# gprs.net
KiCad netlist of a schematic drawn in Altium Designer
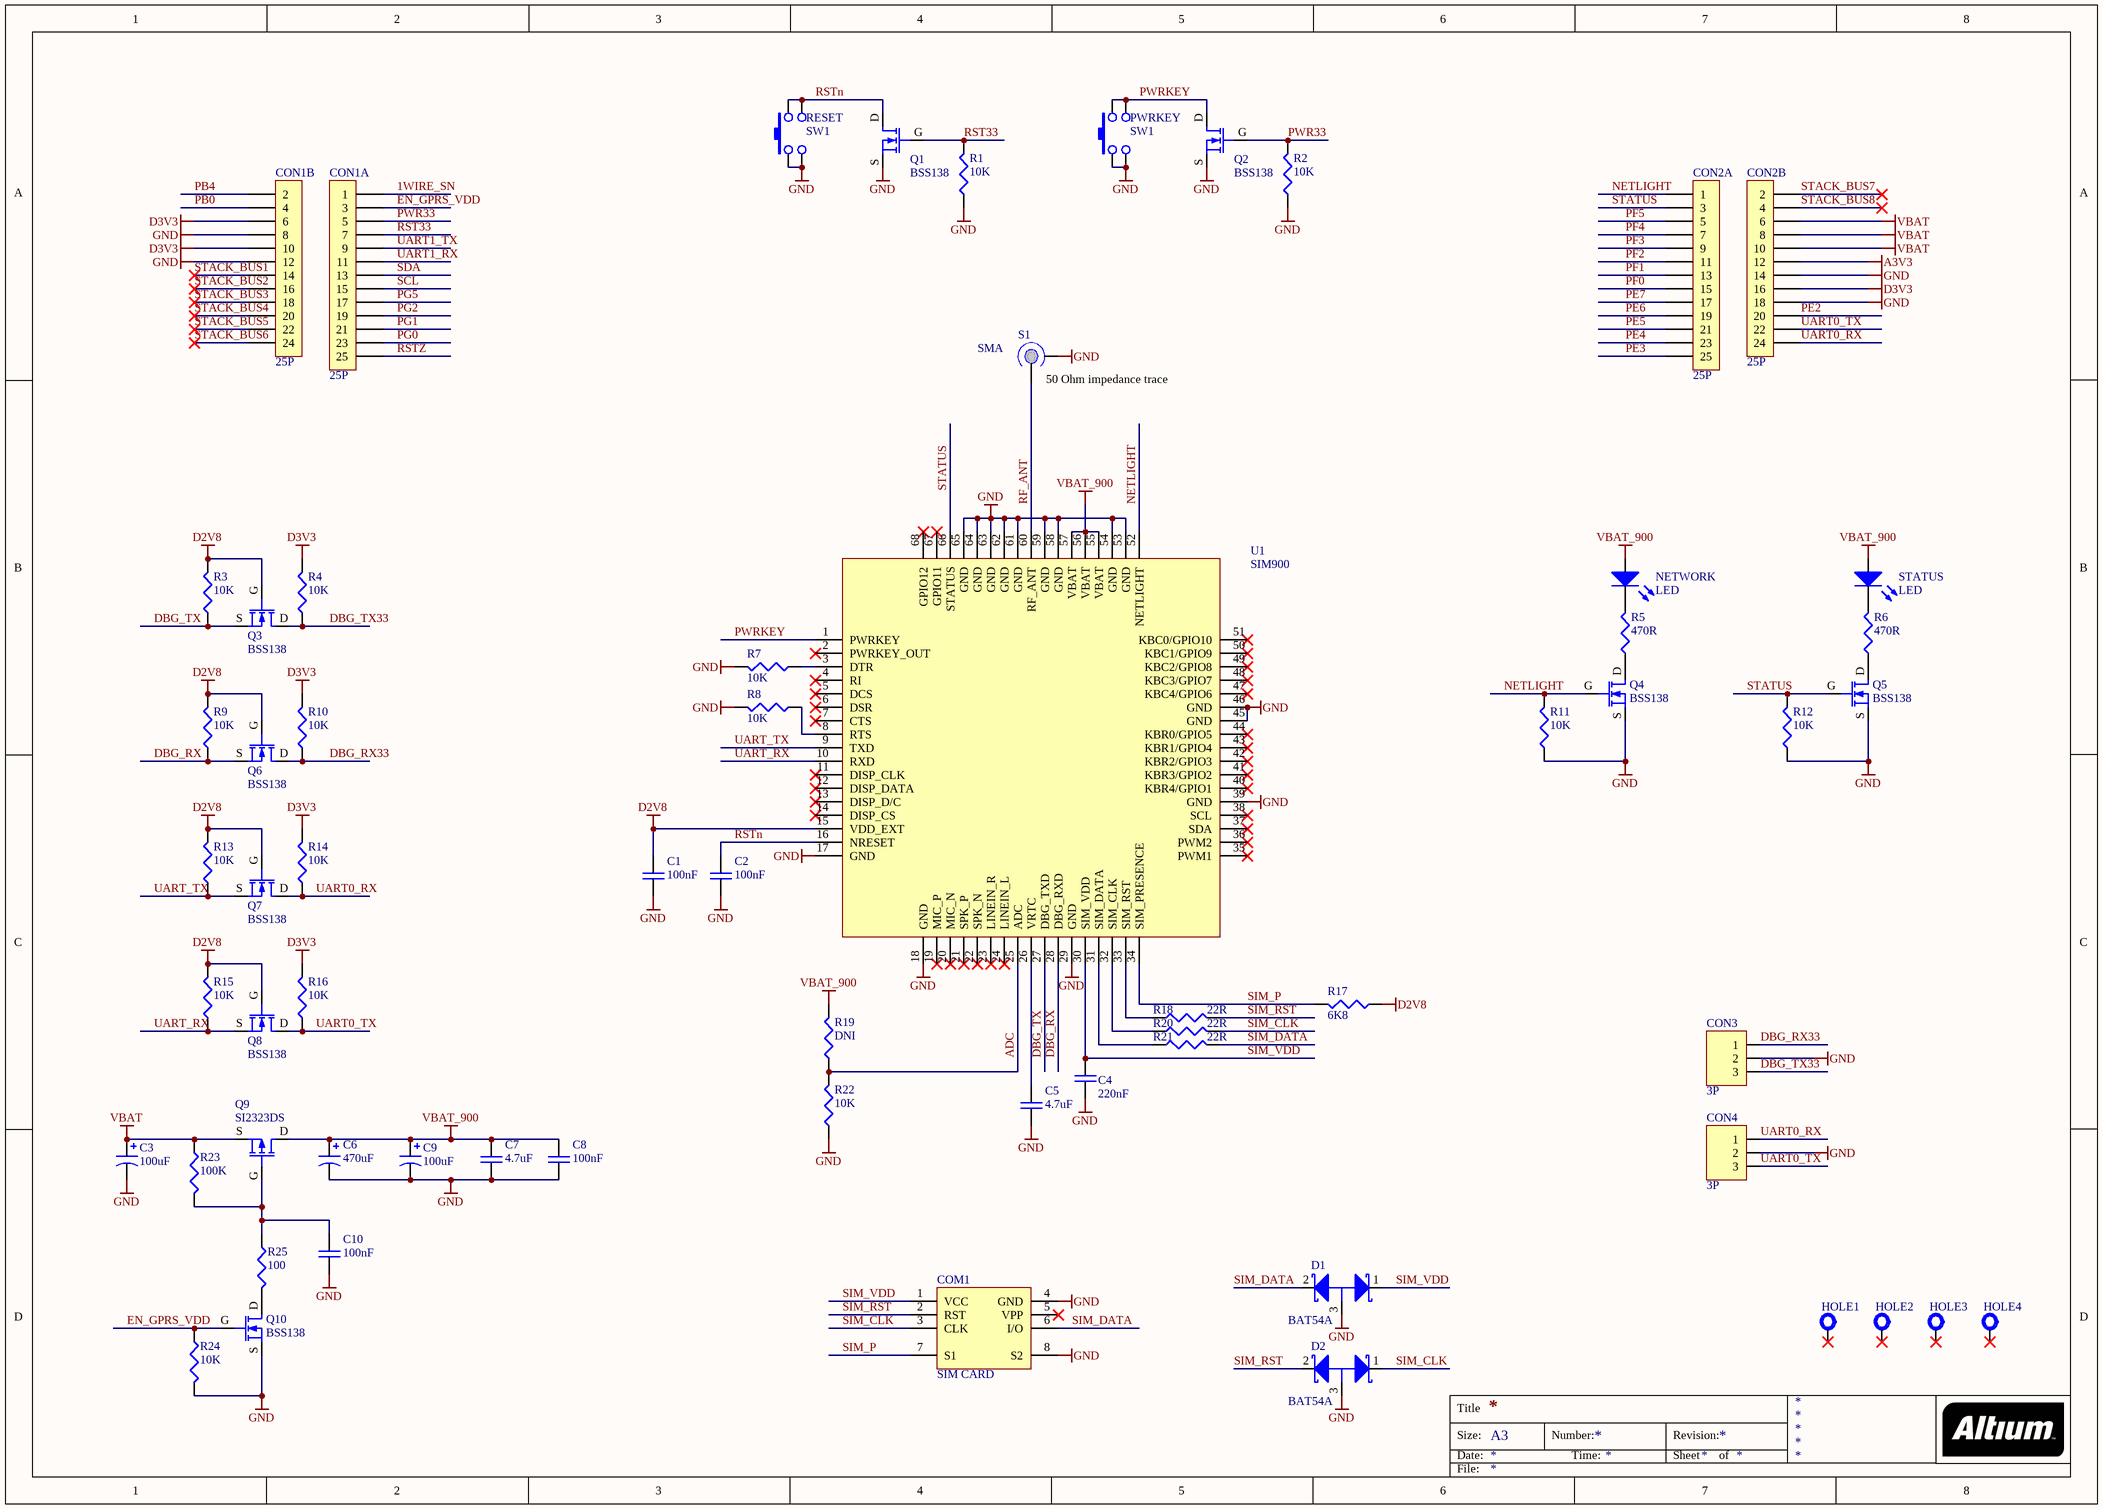
[diagram p0: gprs.SchDoc]

(export (version "E")
  (design (tool "Eeschema 10.0.6"))
  (components
    (comp (ref "C1")
      (value "100nF")
      (footprint "0603")
      (description "Capacitor")
      (fields (field (name "OWNER") "Nuno Brum"))
      (libsource (lib "Alcetronics_Devices") (part "CAP"))
    )
    (comp (ref "C2")
      (value "100nF")
      (footprint "0603")
      (description "Capacitor")
      (fields (field (name "OWNER") "Nuno Brum"))
      (libsource (lib "Alcetronics_Devices") (part "CAP"))
    )
    (comp (ref "C3")
      (value "100uF")
      (footprint "RADIAL-2.5MM")
      (description "Polarized Capacitor")
      (fields (field (name "OWNER") "Nuno Brum"))
      (libsource (lib "Alcetronics_Devices") (part "CAP POL"))
    )
    (comp (ref "C4")
      (value "220nF")
      (footprint "0603")
      (description "Capacitor")
      (fields (field (name "OWNER") "Nuno Brum"))
      (libsource (lib "Alcetronics_Devices") (part "CAP"))
    )
    (comp (ref "C5")
      (value "4.7uF")
      (footprint "0805")
      (description "Capacitor")
      (fields (field (name "OWNER") "Nuno Brum"))
      (libsource (lib "Alcetronics_Devices") (part "CAP"))
    )
    (comp (ref "C6")
      (value "470uF")
      (footprint "CASE-D")
      (description "Polarized Capacitor")
      (fields (field (name "OWNER") "Nuno Brum"))
      (libsource (lib "Alcetronics_Devices") (part "CAP POL"))
    )
    (comp (ref "C7")
      (value "4.7uF")
      (footprint "0805")
      (description "Capacitor")
      (fields (field (name "OWNER") "Nuno Brum"))
      (libsource (lib "Alcetronics_Devices") (part "CAP"))
    )
    (comp (ref "C8")
      (value "100nF")
      (footprint "0603")
      (description "Capacitor")
      (fields (field (name "OWNER") "Nuno Brum"))
      (libsource (lib "Alcetronics_Devices") (part "CAP"))
    )
    (comp (ref "C9")
      (value "100uF")
      (footprint "RADIAL-2.5MM")
      (description "Polarized Capacitor")
      (fields (field (name "OWNER") "Nuno Brum"))
      (libsource (lib "Alcetronics_Devices") (part "CAP POL"))
    )
    (comp (ref "C10")
      (value "100nF")
      (footprint "0603")
      (description "Capacitor")
      (fields (field (name "OWNER") "Nuno Brum"))
      (libsource (lib "Alcetronics_Devices") (part "CAP"))
    )
    (comp (ref "COM1")
      (value "SIM CARD")
      (footprint "Alcetronics_EM:SIMCARD-8")
      (description "SIMCARD holder")
      (fields (field (name "MANUFACTURER") "JAE Electronics"))
      (libsource (lib "Alcetronics_EM") (part "SIMCARD"))
    )
    (comp (ref "CON1")
      (value "25P")
      (footprint "DF9-25-MIRROR")
      (description "Connector 25 Pins")
      (fields (field (name "OWNER") "Ricardo Rodrigues"))
      (libsource (lib "Alcetronics_EM") (part "CON25"))
    )
    (comp (ref "CON2")
      (value "25P")
      (footprint "DF9-25-MIRROR")
      (description "Connector 25 Pins")
      (fields (field (name "OWNER") "Ricardo Rodrigues"))
      (libsource (lib "") (part "CON25_1"))
    )
    (comp (ref "CON3")
      (value "3P")
      (footprint "SIP-3")
      (description "Connector 3 pins")
      (fields (field (name "OWNER") "Rui Rebelo"))
      (libsource (lib "Alcetronics_EM") (part "CON03"))
    )
    (comp (ref "CON4")
      (value "3P")
      (footprint "SIP-3")
      (description "Connector 3 pins")
      (fields (field (name "OWNER") "Rui Rebelo"))
      (libsource (lib "Alcetronics_EM") (part "CON03"))
    )
    (comp (ref "D1")
      (value "BAT54A")
      (footprint "SOT-23")
      (description "Dual Schottky Barrier Diode")
      (fields (field (name "OWNER") "Luis Alves"))
      (libsource (lib "Alcetronics_Devices") (part "BAT54A"))
    )
    (comp (ref "D2")
      (value "BAT54A")
      (footprint "SOT-23")
      (description "Dual Schottky Barrier Diode")
      (fields (field (name "OWNER") "Luis Alves"))
      (libsource (lib "Alcetronics_Devices") (part "BAT54A"))
    )
    (comp (ref "HOLE1")
      (value "HOLE")
      (footprint "NPTH-3MM")
      (description "PCB Fixation Hole M3")
      (fields (field (name "OWNER") "Nuno Brum"))
      (libsource (lib "Alcetronics_EM") (part "PCB HOLE"))
    )
    (comp (ref "HOLE2")
      (value "HOLE")
      (footprint "NPTH-3MM")
      (description "PCB Fixation Hole M3")
      (fields (field (name "OWNER") "Nuno Brum"))
      (libsource (lib "Alcetronics_EM") (part "PCB HOLE"))
    )
    (comp (ref "HOLE3")
      (value "HOLE")
      (footprint "NPTH-3MM")
      (description "PCB Fixation Hole M3")
      (fields (field (name "OWNER") "Nuno Brum"))
      (libsource (lib "Alcetronics_EM") (part "PCB HOLE"))
    )
    (comp (ref "HOLE4")
      (value "HOLE")
      (footprint "NPTH-3MM")
      (description "PCB Fixation Hole M3")
      (fields (field (name "OWNER") "Nuno Brum"))
      (libsource (lib "Alcetronics_EM") (part "PCB HOLE"))
    )
    (comp (ref "NETWORK")
      (value "LED")
      (footprint "0805@DIODE")
      (description "Light emitting diode")
      (fields (field (name "OWNER") "Nuno Brum"))
      (libsource (lib "Alcetronics_Devices") (part "LED"))
    )
    (comp (ref "PWRKEY")
      (value "SW1")
      (footprint "MICROSWITCH")
      (description "Switch Push Button")
      (fields (field (name "OWNER") "Nuno Brum"))
      (libsource (lib "Alcetronics_EM") (part "SW1"))
    )
    (comp (ref "Q1")
      (value "BSS138")
      (footprint "SOT-23@GSD")
      (description "N-Channel Logic Level Enhancement Mode Field Effect Transistor")
      (fields (field (name "OWNER") "Nuno Brum"))
      (libsource (lib "Alcetronics_Devices") (part "MOSFET-N"))
    )
    (comp (ref "Q2")
      (value "BSS138")
      (footprint "SOT-23@GSD")
      (description "N-Channel Logic Level Enhancement Mode Field Effect Transistor")
      (fields (field (name "OWNER") "Nuno Brum"))
      (libsource (lib "Alcetronics_Devices") (part "MOSFET-N"))
    )
    (comp (ref "Q3")
      (value "BSS138")
      (footprint "SOT-23@GSD")
      (description "N-Channel Logic Level Enhancement Mode Field Effect Transistor")
      (fields (field (name "OWNER") "Nuno Brum"))
      (libsource (lib "Alcetronics_Devices") (part "MOSFET-N"))
    )
    (comp (ref "Q4")
      (value "BSS138")
      (footprint "SOT-23@GSD")
      (description "N-Channel Logic Level Enhancement Mode Field Effect Transistor")
      (fields (field (name "OWNER") "Nuno Brum"))
      (libsource (lib "Alcetronics_Devices") (part "MOSFET-N"))
    )
    (comp (ref "Q5")
      (value "BSS138")
      (footprint "SOT-23@GSD")
      (description "N-Channel Logic Level Enhancement Mode Field Effect Transistor")
      (fields (field (name "OWNER") "Nuno Brum"))
      (libsource (lib "Alcetronics_Devices") (part "MOSFET-N"))
    )
    (comp (ref "Q6")
      (value "BSS138")
      (footprint "SOT-23@GSD")
      (description "N-Channel Logic Level Enhancement Mode Field Effect Transistor")
      (fields (field (name "OWNER") "Nuno Brum"))
      (libsource (lib "Alcetronics_Devices") (part "MOSFET-N"))
    )
    (comp (ref "Q7")
      (value "BSS138")
      (footprint "SOT-23@GSD")
      (description "N-Channel Logic Level Enhancement Mode Field Effect Transistor")
      (fields (field (name "OWNER") "Nuno Brum"))
      (libsource (lib "Alcetronics_Devices") (part "MOSFET-N"))
    )
    (comp (ref "Q8")
      (value "BSS138")
      (footprint "SOT-23@GSD")
      (description "N-Channel Logic Level Enhancement Mode Field Effect Transistor")
      (fields (field (name "OWNER") "Nuno Brum"))
      (libsource (lib "Alcetronics_Devices") (part "MOSFET-N"))
    )
    (comp (ref "Q9")
      (value "SI2323DS")
      (footprint "SOT-23@GSD")
      (description "P-Channel Logic Level Enhancement Mode Field Effect Transistor")
      (fields (field (name "OWNER") "Nuno Brum"))
      (libsource (lib "Alcetronics_Devices") (part "MOSFET-P"))
    )
    (comp (ref "Q10")
      (value "BSS138")
      (footprint "SOT-23@GSD")
      (description "N-Channel Logic Level Enhancement Mode Field Effect Transistor")
      (fields (field (name "OWNER") "Nuno Brum"))
      (libsource (lib "Alcetronics_Devices") (part "MOSFET-N"))
    )
    (comp (ref "R1")
      (value "10K")
      (footprint "0603")
      (description "Resistor")
      (fields (field (name "OWNER") "Nuno Brum"))
      (libsource (lib "Alcetronics_Devices") (part "RES"))
    )
    (comp (ref "R2")
      (value "10K")
      (footprint "0603")
      (description "Resistor")
      (fields (field (name "OWNER") "Nuno Brum"))
      (libsource (lib "Alcetronics_Devices") (part "RES"))
    )
    (comp (ref "R3")
      (value "10K")
      (footprint "0603")
      (description "Resistor")
      (fields (field (name "OWNER") "Nuno Brum"))
      (libsource (lib "Alcetronics_Devices") (part "RES"))
    )
    (comp (ref "R4")
      (value "10K")
      (footprint "0603")
      (description "Resistor")
      (fields (field (name "OWNER") "Nuno Brum"))
      (libsource (lib "Alcetronics_Devices") (part "RES"))
    )
    (comp (ref "R5")
      (value "470R")
      (footprint "0603")
      (description "Resistor")
      (fields (field (name "OWNER") "Nuno Brum"))
      (libsource (lib "Alcetronics_Devices") (part "RES"))
    )
    (comp (ref "R6")
      (value "470R")
      (footprint "0603")
      (description "Resistor")
      (fields (field (name "OWNER") "Nuno Brum"))
      (libsource (lib "Alcetronics_Devices") (part "RES"))
    )
    (comp (ref "R7")
      (value "10K")
      (footprint "0603")
      (description "Resistor")
      (fields (field (name "OWNER") "Nuno Brum"))
      (libsource (lib "Alcetronics_Devices") (part "RES"))
    )
    (comp (ref "R8")
      (value "10K")
      (footprint "0603")
      (description "Resistor")
      (fields (field (name "OWNER") "Nuno Brum"))
      (libsource (lib "Alcetronics_Devices") (part "RES"))
    )
    (comp (ref "R9")
      (value "10K")
      (footprint "0603")
      (description "Resistor")
      (fields (field (name "OWNER") "Nuno Brum"))
      (libsource (lib "Alcetronics_Devices") (part "RES"))
    )
    (comp (ref "R10")
      (value "10K")
      (footprint "0603")
      (description "Resistor")
      (fields (field (name "OWNER") "Nuno Brum"))
      (libsource (lib "Alcetronics_Devices") (part "RES"))
    )
    (comp (ref "R11")
      (value "10K")
      (footprint "0603")
      (description "Resistor")
      (fields (field (name "OWNER") "Nuno Brum"))
      (libsource (lib "Alcetronics_Devices") (part "RES"))
    )
    (comp (ref "R12")
      (value "10K")
      (footprint "0603")
      (description "Resistor")
      (fields (field (name "OWNER") "Nuno Brum"))
      (libsource (lib "Alcetronics_Devices") (part "RES"))
    )
    (comp (ref "R13")
      (value "10K")
      (footprint "0603")
      (description "Resistor")
      (fields (field (name "OWNER") "Nuno Brum"))
      (libsource (lib "Alcetronics_Devices") (part "RES"))
    )
    (comp (ref "R14")
      (value "10K")
      (footprint "0603")
      (description "Resistor")
      (fields (field (name "OWNER") "Nuno Brum"))
      (libsource (lib "Alcetronics_Devices") (part "RES"))
    )
    (comp (ref "R15")
      (value "10K")
      (footprint "0603")
      (description "Resistor")
      (fields (field (name "OWNER") "Nuno Brum"))
      (libsource (lib "Alcetronics_Devices") (part "RES"))
    )
    (comp (ref "R16")
      (value "10K")
      (footprint "0603")
      (description "Resistor")
      (fields (field (name "OWNER") "Nuno Brum"))
      (libsource (lib "Alcetronics_Devices") (part "RES"))
    )
    (comp (ref "R17")
      (value "6K8")
      (footprint "0603")
      (description "Resistor")
      (fields (field (name "OWNER") "Nuno Brum"))
      (libsource (lib "Alcetronics_Devices") (part "RES"))
    )
    (comp (ref "R18")
      (value "22R")
      (footprint "0603")
      (description "Resistor")
      (fields (field (name "OWNER") "Nuno Brum"))
      (libsource (lib "Alcetronics_Devices") (part "RES"))
    )
    (comp (ref "R19")
      (value "DNI")
      (footprint "0603")
      (description "Resistor")
      (fields (field (name "OWNER") "Nuno Brum"))
      (libsource (lib "Alcetronics_Devices") (part "RES"))
    )
    (comp (ref "R20")
      (value "22R")
      (footprint "0603")
      (description "Resistor")
      (fields (field (name "OWNER") "Nuno Brum"))
      (libsource (lib "Alcetronics_Devices") (part "RES"))
    )
    (comp (ref "R21")
      (value "22R")
      (footprint "0603")
      (description "Resistor")
      (fields (field (name "OWNER") "Nuno Brum"))
      (libsource (lib "Alcetronics_Devices") (part "RES"))
    )
    (comp (ref "R22")
      (value "10K")
      (footprint "0603")
      (description "Resistor")
      (fields (field (name "OWNER") "Nuno Brum"))
      (libsource (lib "Alcetronics_Devices") (part "RES"))
    )
    (comp (ref "R23")
      (value "100K")
      (footprint "0603")
      (description "Resistor")
      (fields (field (name "OWNER") "Nuno Brum"))
      (libsource (lib "Alcetronics_Devices") (part "RES"))
    )
    (comp (ref "R24")
      (value "10K")
      (footprint "0603")
      (description "Resistor")
      (fields (field (name "OWNER") "Nuno Brum"))
      (libsource (lib "Alcetronics_Devices") (part "RES"))
    )
    (comp (ref "R25")
      (value "100")
      (footprint "0603")
      (description "Resistor")
      (fields (field (name "OWNER") "Nuno Brum"))
      (libsource (lib "Alcetronics_Devices") (part "RES"))
    )
    (comp (ref "RESET")
      (value "SW1")
      (footprint "MICROSWITCH")
      (description "Switch Push Button")
      (fields (field (name "OWNER") "Nuno Brum"))
      (libsource (lib "Alcetronics_EM") (part "SW1"))
    )
    (comp (ref "S1")
      (value "SMA")
      (footprint "SMA-JOHNSON-SCREW")
      (description "SMA to PCB - Coaxial connector")
      (fields (field (name "OWNER") "Nuno Brum"))
      (libsource (lib "Alcetronics_EM") (part "SMA"))
    )
    (comp (ref "STATUS")
      (value "LED")
      (footprint "0805@DIODE")
      (description "Light emitting diode")
      (fields (field (name "OWNER") "Nuno Brum"))
      (libsource (lib "Alcetronics_Devices") (part "LED"))
    )
    (comp (ref "U1") (value "SIM900") (footprint "SIM900") (libsource (lib "Alcetronics_IC") (part "SIM900")))
  )
  (nets
    (net (code "1") (name "/1WIRE_SN") (class "Default")
      (node (ref "CON1") (pin "1") (pinfunction "1_1") (pintype "passive"))
    )
    (net (code "2") (name "/ADC") (class "Default")
      (node (ref "R19") (pin "1") (pinfunction "1_1") (pintype "passive"))
      (node (ref "R22") (pin "2") (pinfunction "2_2") (pintype "passive"))
      (node (ref "U1") (pin "25") (pinfunction "ADC_25") (pintype "passive"))
    )
    (net (code "3") (name "/DBG_RX") (class "Default")
      (node (ref "Q6") (pin "S") (pinfunction "S_S") (pintype "passive"))
      (node (ref "R9") (pin "1") (pinfunction "1_1") (pintype "passive"))
      (node (ref "U1") (pin "28") (pinfunction "DBG_RXD_28") (pintype "passive"))
    )
    (net (code "4") (name "/DBG_RX33") (class "Default")
      (node (ref "CON3") (pin "1") (pinfunction "1_1") (pintype "passive"))
      (node (ref "Q6") (pin "D") (pinfunction "D_D") (pintype "passive"))
      (node (ref "R10") (pin "1") (pinfunction "1_1") (pintype "passive"))
    )
    (net (code "5") (name "/DBG_TX") (class "Default")
      (node (ref "Q3") (pin "S") (pinfunction "S_S") (pintype "passive"))
      (node (ref "R3") (pin "1") (pinfunction "1_1") (pintype "passive"))
      (node (ref "U1") (pin "27") (pinfunction "DBG_TXD_27") (pintype "passive"))
    )
    (net (code "6") (name "/DBG_TX33") (class "Default")
      (node (ref "CON3") (pin "3") (pinfunction "3_3") (pintype "passive"))
      (node (ref "Q3") (pin "D") (pinfunction "D_D") (pintype "passive"))
      (node (ref "R4") (pin "1") (pinfunction "1_1") (pintype "passive"))
    )
    (net (code "7") (name "/EN_GPRS_VDD") (class "Default")
      (node (ref "CON1") (pin "3") (pinfunction "3_3") (pintype "passive"))
      (node (ref "Q10") (pin "G") (pinfunction "G_G") (pintype "passive"))
      (node (ref "R24") (pin "1") (pinfunction "1_1") (pintype "passive"))
    )
    (net (code "8") (name "/NETLIGHT") (class "Default")
      (node (ref "CON2") (pin "1") (pinfunction "1_1") (pintype "passive"))
      (node (ref "Q4") (pin "G") (pinfunction "G_G") (pintype "passive"))
      (node (ref "R11") (pin "2") (pinfunction "2_2") (pintype "passive"))
      (node (ref "U1") (pin "52") (pinfunction "NETLIGHT_52") (pintype "passive"))
    )
    (net (code "9") (name "/PB0") (class "Default")
      (node (ref "CON1") (pin "4") (pinfunction "4_4") (pintype "passive"))
    )
    (net (code "10") (name "/PB4") (class "Default")
      (node (ref "CON1") (pin "2") (pinfunction "2_2") (pintype "passive"))
    )
    (net (code "11") (name "/PE2") (class "Default")
      (node (ref "CON2") (pin "20") (pinfunction "20_20") (pintype "passive"))
    )
    (net (code "12") (name "/PE3") (class "Default")
      (node (ref "CON2") (pin "25") (pinfunction "25_25") (pintype "passive"))
    )
    (net (code "13") (name "/PE4") (class "Default")
      (node (ref "CON2") (pin "23") (pinfunction "23_23") (pintype "passive"))
    )
    (net (code "14") (name "/PE5") (class "Default")
      (node (ref "CON2") (pin "21") (pinfunction "21_21") (pintype "passive"))
    )
    (net (code "15") (name "/PE6") (class "Default")
      (node (ref "CON2") (pin "19") (pinfunction "19_19") (pintype "passive"))
    )
    (net (code "16") (name "/PE7") (class "Default")
      (node (ref "CON2") (pin "17") (pinfunction "17_17") (pintype "passive"))
    )
    (net (code "17") (name "/PF0") (class "Default")
      (node (ref "CON2") (pin "15") (pinfunction "15_15") (pintype "passive"))
    )
    (net (code "18") (name "/PF1") (class "Default")
      (node (ref "CON2") (pin "13") (pinfunction "13_13") (pintype "passive"))
    )
    (net (code "19") (name "/PF2") (class "Default")
      (node (ref "CON2") (pin "11") (pinfunction "11_11") (pintype "passive"))
    )
    (net (code "20") (name "/PF3") (class "Default")
      (node (ref "CON2") (pin "9") (pinfunction "9_9") (pintype "passive"))
    )
    (net (code "21") (name "/PF4") (class "Default")
      (node (ref "CON2") (pin "7") (pinfunction "7_7") (pintype "passive"))
    )
    (net (code "22") (name "/PF5") (class "Default")
      (node (ref "CON2") (pin "5") (pinfunction "5_5") (pintype "passive"))
    )
    (net (code "23") (name "/PG0") (class "Default")
      (node (ref "CON1") (pin "23") (pinfunction "23_23") (pintype "passive"))
    )
    (net (code "24") (name "/PG1") (class "Default")
      (node (ref "CON1") (pin "21") (pinfunction "21_21") (pintype "passive"))
    )
    (net (code "25") (name "/PG2") (class "Default")
      (node (ref "CON1") (pin "19") (pinfunction "19_19") (pintype "passive"))
    )
    (net (code "26") (name "/PG5") (class "Default")
      (node (ref "CON1") (pin "17") (pinfunction "17_17") (pintype "passive"))
    )
    (net (code "27") (name "/PWR33") (class "Default")
      (node (ref "CON1") (pin "5") (pinfunction "5_5") (pintype "passive"))
      (node (ref "Q2") (pin "G") (pinfunction "G_G") (pintype "passive"))
      (node (ref "R2") (pin "2") (pinfunction "2_2") (pintype "passive"))
    )
    (net (code "28") (name "/PWRKEY") (class "Default")
      (node (ref "PWRKEY") (pin "2") (pinfunction "2_2") (pintype "passive"))
      (node (ref "PWRKEY") (pin "4") (pinfunction "4_4") (pintype "passive"))
      (node (ref "Q2") (pin "D") (pinfunction "D_D") (pintype "passive"))
      (node (ref "U1") (pin "1") (pinfunction "PWRKEY_1") (pintype "passive"))
    )
    (net (code "29") (name "/RF_ANT") (class "Default")
      (node (ref "S1") (pin "1") (pinfunction "SIG_1") (pintype "passive"))
      (node (ref "U1") (pin "60") (pinfunction "RF_ANT_60") (pintype "passive"))
    )
    (net (code "30") (name "/RST33") (class "Default")
      (node (ref "CON1") (pin "7") (pinfunction "7_7") (pintype "passive"))
      (node (ref "Q1") (pin "G") (pinfunction "G_G") (pintype "passive"))
      (node (ref "R1") (pin "2") (pinfunction "2_2") (pintype "passive"))
    )
    (net (code "31") (name "/RSTZ") (class "Default")
      (node (ref "CON1") (pin "25") (pinfunction "25_25") (pintype "passive"))
    )
    (net (code "32") (name "/RSTn") (class "Default")
      (node (ref "C2") (pin "2") (pinfunction "2_2") (pintype "passive"))
      (node (ref "Q1") (pin "D") (pinfunction "D_D") (pintype "passive"))
      (node (ref "RESET") (pin "2") (pinfunction "2_2") (pintype "passive"))
      (node (ref "RESET") (pin "4") (pinfunction "4_4") (pintype "passive"))
      (node (ref "U1") (pin "16") (pinfunction "NRESET_16") (pintype "passive"))
    )
    (net (code "33") (name "/SCL") (class "Default")
      (node (ref "CON1") (pin "15") (pinfunction "15_15") (pintype "passive"))
    )
    (net (code "34") (name "/SDA") (class "Default")
      (node (ref "CON1") (pin "13") (pinfunction "13_13") (pintype "passive"))
    )
    (net (code "35") (name "/SIM_CLK") (class "Default")
      (node (ref "COM1") (pin "3") (pinfunction "CLK_3") (pintype "passive"))
      (node (ref "D2") (pin "1") (pinfunction "A1_1") (pintype "passive"))
      (node (ref "R20") (pin "2") (pinfunction "2_2") (pintype "passive"))
    )
    (net (code "36") (name "/SIM_DATA") (class "Default")
      (node (ref "COM1") (pin "6") (pinfunction "I/O_6") (pintype "passive"))
      (node (ref "D1") (pin "2") (pinfunction "A2_2") (pintype "passive"))
      (node (ref "R21") (pin "2") (pinfunction "2_2") (pintype "passive"))
    )
    (net (code "37") (name "/SIM_P") (class "Default")
      (node (ref "COM1") (pin "7") (pinfunction "S1_7") (pintype "passive"))
      (node (ref "R17") (pin "2") (pinfunction "2_2") (pintype "passive"))
      (node (ref "U1") (pin "34") (pinfunction "SIM_PRESENCE_34") (pintype "passive"))
    )
    (net (code "38") (name "/SIM_RST") (class "Default")
      (node (ref "COM1") (pin "2") (pinfunction "RST_2") (pintype "passive"))
      (node (ref "D2") (pin "2") (pinfunction "A2_2") (pintype "passive"))
      (node (ref "R18") (pin "2") (pinfunction "2_2") (pintype "passive"))
    )
    (net (code "39") (name "/SIM_VDD") (class "Default")
      (node (ref "C4") (pin "2") (pinfunction "2_2") (pintype "passive"))
      (node (ref "COM1") (pin "1") (pinfunction "VCC_1") (pintype "passive"))
      (node (ref "D1") (pin "1") (pinfunction "A1_1") (pintype "passive"))
      (node (ref "U1") (pin "30") (pinfunction "SIM_VDD_30") (pintype "passive"))
    )
    (net (code "40") (name "/STACK_BUS1") (class "Default")
      (node (ref "CON1") (pin "14") (pinfunction "14_14") (pintype "passive+no_connect"))
    )
    (net (code "41") (name "/STACK_BUS2") (class "Default")
      (node (ref "CON1") (pin "16") (pinfunction "16_16") (pintype "passive+no_connect"))
    )
    (net (code "42") (name "/STACK_BUS3") (class "Default")
      (node (ref "CON1") (pin "18") (pinfunction "18_18") (pintype "passive+no_connect"))
    )
    (net (code "43") (name "/STACK_BUS4") (class "Default")
      (node (ref "CON1") (pin "20") (pinfunction "20_20") (pintype "passive+no_connect"))
    )
    (net (code "44") (name "/STACK_BUS5") (class "Default")
      (node (ref "CON1") (pin "22") (pinfunction "22_22") (pintype "passive+no_connect"))
    )
    (net (code "45") (name "/STACK_BUS6") (class "Default")
      (node (ref "CON1") (pin "24") (pinfunction "24_24") (pintype "passive+no_connect"))
    )
    (net (code "46") (name "/STACK_BUS7") (class "Default")
      (node (ref "CON2") (pin "2") (pinfunction "2_2") (pintype "passive+no_connect"))
    )
    (net (code "47") (name "/STACK_BUS8") (class "Default")
      (node (ref "CON2") (pin "4") (pinfunction "4_4") (pintype "passive+no_connect"))
    )
    (net (code "48") (name "/STATUS") (class "Default")
      (node (ref "CON2") (pin "3") (pinfunction "3_3") (pintype "passive"))
      (node (ref "Q5") (pin "G") (pinfunction "G_G") (pintype "passive"))
      (node (ref "R12") (pin "2") (pinfunction "2_2") (pintype "passive"))
      (node (ref "U1") (pin "66") (pinfunction "STATUS_66") (pintype "passive"))
    )
    (net (code "49") (name "/UART0_RX") (class "Default")
      (node (ref "CON2") (pin "24") (pinfunction "24_24") (pintype "passive"))
      (node (ref "CON4") (pin "1") (pinfunction "1_1") (pintype "passive"))
      (node (ref "Q7") (pin "D") (pinfunction "D_D") (pintype "passive"))
      (node (ref "R14") (pin "1") (pinfunction "1_1") (pintype "passive"))
    )
    (net (code "50") (name "/UART0_TX") (class "Default")
      (node (ref "CON2") (pin "22") (pinfunction "22_22") (pintype "passive"))
      (node (ref "CON4") (pin "3") (pinfunction "3_3") (pintype "passive"))
      (node (ref "Q8") (pin "D") (pinfunction "D_D") (pintype "passive"))
      (node (ref "R16") (pin "1") (pinfunction "1_1") (pintype "passive"))
    )
    (net (code "51") (name "/UART1_RX") (class "Default")
      (node (ref "CON1") (pin "11") (pinfunction "11_11") (pintype "passive"))
    )
    (net (code "52") (name "/UART1_TX") (class "Default")
      (node (ref "CON1") (pin "9") (pinfunction "9_9") (pintype "passive"))
    )
    (net (code "53") (name "/UART_RX") (class "Default")
      (node (ref "Q8") (pin "S") (pinfunction "S_S") (pintype "passive"))
      (node (ref "R15") (pin "1") (pinfunction "1_1") (pintype "passive"))
      (node (ref "U1") (pin "10") (pinfunction "RXD_10") (pintype "passive"))
    )
    (net (code "54") (name "/UART_TX") (class "Default")
      (node (ref "Q7") (pin "S") (pinfunction "S_S") (pintype "passive"))
      (node (ref "R13") (pin "1") (pinfunction "1_1") (pintype "passive"))
      (node (ref "U1") (pin "9") (pinfunction "TXD_9") (pintype "passive"))
    )
    (net (code "55") (name "A3V3") (class "Default")
      (node (ref "CON2") (pin "12") (pinfunction "12_12") (pintype "passive"))
    )
    (net (code "56") (name "D2V8") (class "Default")
      (node (ref "C1") (pin "2") (pinfunction "2_2") (pintype "passive"))
      (node (ref "Q3") (pin "G") (pinfunction "G_G") (pintype "passive"))
      (node (ref "Q6") (pin "G") (pinfunction "G_G") (pintype "passive"))
      (node (ref "Q7") (pin "G") (pinfunction "G_G") (pintype "passive"))
      (node (ref "Q8") (pin "G") (pinfunction "G_G") (pintype "passive"))
      (node (ref "R13") (pin "2") (pinfunction "2_2") (pintype "passive"))
      (node (ref "R15") (pin "2") (pinfunction "2_2") (pintype "passive"))
      (node (ref "R17") (pin "1") (pinfunction "1_1") (pintype "passive"))
      (node (ref "R3") (pin "2") (pinfunction "2_2") (pintype "passive"))
      (node (ref "R9") (pin "2") (pinfunction "2_2") (pintype "passive"))
      (node (ref "U1") (pin "15") (pinfunction "VDD_EXT_15") (pintype "passive"))
    )
    (net (code "57") (name "D3V3") (class "Default")
      (node (ref "CON1") (pin "10") (pinfunction "10_10") (pintype "passive"))
      (node (ref "CON1") (pin "6") (pinfunction "6_6") (pintype "passive"))
      (node (ref "CON2") (pin "16") (pinfunction "16_16") (pintype "passive"))
      (node (ref "R10") (pin "2") (pinfunction "2_2") (pintype "passive"))
      (node (ref "R14") (pin "2") (pinfunction "2_2") (pintype "passive"))
      (node (ref "R16") (pin "2") (pinfunction "2_2") (pintype "passive"))
      (node (ref "R4") (pin "2") (pinfunction "2_2") (pintype "passive"))
    )
    (net (code "58") (name "GND") (class "Default")
      (node (ref "C1") (pin "1") (pinfunction "1_1") (pintype "passive"))
      (node (ref "C10") (pin "1") (pinfunction "1_1") (pintype "passive"))
      (node (ref "C2") (pin "1") (pinfunction "1_1") (pintype "passive"))
      (node (ref "C3") (pin "2") (pinfunction "N_2") (pintype "passive"))
      (node (ref "C4") (pin "1") (pinfunction "1_1") (pintype "passive"))
      (node (ref "C5") (pin "1") (pinfunction "1_1") (pintype "passive"))
      (node (ref "C6") (pin "2") (pinfunction "N_2") (pintype "passive"))
      (node (ref "C7") (pin "1") (pinfunction "1_1") (pintype "passive"))
      (node (ref "C8") (pin "1") (pinfunction "1_1") (pintype "passive"))
      (node (ref "C9") (pin "2") (pinfunction "N_2") (pintype "passive"))
      (node (ref "COM1") (pin "4") (pinfunction "GND_4") (pintype "passive"))
      (node (ref "COM1") (pin "8") (pinfunction "S2_8") (pintype "passive"))
      (node (ref "CON1") (pin "12") (pinfunction "12_12") (pintype "passive"))
      (node (ref "CON1") (pin "8") (pinfunction "8_8") (pintype "passive"))
      (node (ref "CON2") (pin "14") (pinfunction "14_14") (pintype "passive"))
      (node (ref "CON2") (pin "18") (pinfunction "18_18") (pintype "passive"))
      (node (ref "CON3") (pin "2") (pinfunction "2_2") (pintype "passive"))
      (node (ref "CON4") (pin "2") (pinfunction "2_2") (pintype "passive"))
      (node (ref "D1") (pin "3") (pinfunction "K_3") (pintype "passive"))
      (node (ref "D2") (pin "3") (pinfunction "K_3") (pintype "passive"))
      (node (ref "PWRKEY") (pin "1") (pinfunction "1_1") (pintype "passive"))
      (node (ref "PWRKEY") (pin "3") (pinfunction "3_3") (pintype "passive"))
      (node (ref "Q1") (pin "S") (pinfunction "S_S") (pintype "passive"))
      (node (ref "Q10") (pin "S") (pinfunction "S_S") (pintype "passive"))
      (node (ref "Q2") (pin "S") (pinfunction "S_S") (pintype "passive"))
      (node (ref "Q4") (pin "S") (pinfunction "S_S") (pintype "passive"))
      (node (ref "Q5") (pin "S") (pinfunction "S_S") (pintype "passive"))
      (node (ref "R1") (pin "1") (pinfunction "1_1") (pintype "passive"))
      (node (ref "R11") (pin "1") (pinfunction "1_1") (pintype "passive"))
      (node (ref "R12") (pin "1") (pinfunction "1_1") (pintype "passive"))
      (node (ref "R2") (pin "1") (pinfunction "1_1") (pintype "passive"))
      (node (ref "R22") (pin "1") (pinfunction "1_1") (pintype "passive"))
      (node (ref "R24") (pin "2") (pinfunction "2_2") (pintype "passive"))
      (node (ref "R7") (pin "2") (pinfunction "2_2") (pintype "passive"))
      (node (ref "R8") (pin "2") (pinfunction "2_2") (pintype "passive"))
      (node (ref "RESET") (pin "1") (pinfunction "1_1") (pintype "passive"))
      (node (ref "RESET") (pin "3") (pinfunction "3_3") (pintype "passive"))
      (node (ref "S1") (pin "2") (pinfunction "GND_2") (pintype "passive"))
      (node (ref "U1") (pin "17") (pinfunction "GND_17") (pintype "passive"))
      (node (ref "U1") (pin "18") (pinfunction "GND_18") (pintype "passive"))
      (node (ref "U1") (pin "29") (pinfunction "GND_29") (pintype "passive"))
      (node (ref "U1") (pin "39") (pinfunction "GND_39") (pintype "passive"))
      (node (ref "U1") (pin "45") (pinfunction "GND_45") (pintype "passive"))
      (node (ref "U1") (pin "46") (pinfunction "GND_46") (pintype "passive"))
      (node (ref "U1") (pin "53") (pinfunction "GND_53") (pintype "passive"))
      (node (ref "U1") (pin "54") (pinfunction "GND_54") (pintype "passive"))
      (node (ref "U1") (pin "58") (pinfunction "GND_58") (pintype "passive"))
      (node (ref "U1") (pin "59") (pinfunction "GND_59") (pintype "passive"))
      (node (ref "U1") (pin "61") (pinfunction "GND_61") (pintype "passive"))
      (node (ref "U1") (pin "62") (pinfunction "GND_62") (pintype "passive"))
      (node (ref "U1") (pin "63") (pinfunction "GND_63") (pintype "passive"))
      (node (ref "U1") (pin "64") (pinfunction "GND_64") (pintype "passive"))
      (node (ref "U1") (pin "65") (pinfunction "GND_65") (pintype "passive"))
    )
    (net (code "59") (name "Net-(C10-Pad2)") (class "Default")
      (node (ref "C10") (pin "2") (pinfunction "2_2") (pintype "passive"))
      (node (ref "Q9") (pin "G") (pinfunction "G_G") (pintype "passive"))
      (node (ref "R23") (pin "2") (pinfunction "2_2") (pintype "passive"))
      (node (ref "R25") (pin "1") (pinfunction "1_1") (pintype "passive"))
    )
    (net (code "60") (name "Net-(NETWORK-PadK)") (class "Default")
      (node (ref "NETWORK") (pin "K") (pinfunction "K_K") (pintype "passive"))
      (node (ref "R5") (pin "2") (pinfunction "2_2") (pintype "passive"))
    )
    (net (code "61") (name "Net-(Q4-PadD)") (class "Default")
      (node (ref "Q4") (pin "D") (pinfunction "D_D") (pintype "passive"))
      (node (ref "R5") (pin "1") (pinfunction "1_1") (pintype "passive"))
    )
    (net (code "62") (name "Net-(Q5-PadD)") (class "Default")
      (node (ref "Q5") (pin "D") (pinfunction "D_D") (pintype "passive"))
      (node (ref "R6") (pin "1") (pinfunction "1_1") (pintype "passive"))
    )
    (net (code "63") (name "Net-(Q10-PadD)") (class "Default")
      (node (ref "Q10") (pin "D") (pinfunction "D_D") (pintype "passive"))
      (node (ref "R25") (pin "2") (pinfunction "2_2") (pintype "passive"))
    )
    (net (code "64") (name "Net-(R6-Pad2)") (class "Default")
      (node (ref "R6") (pin "2") (pinfunction "2_2") (pintype "passive"))
      (node (ref "STATUS") (pin "K") (pinfunction "K_K") (pintype "passive"))
    )
    (net (code "65") (name "Net-(U1-DTR)") (class "Default")
      (node (ref "R7") (pin "1") (pinfunction "1_1") (pintype "passive"))
      (node (ref "U1") (pin "3") (pinfunction "DTR_3") (pintype "passive"))
    )
    (net (code "66") (name "Net-(U1-RTS)") (class "Default")
      (node (ref "R8") (pin "1") (pinfunction "1_1") (pintype "passive"))
      (node (ref "U1") (pin "8") (pinfunction "RTS_8") (pintype "passive"))
    )
    (net (code "67") (name "Net-(U1-SIM_CLK)") (class "Default")
      (node (ref "R20") (pin "1") (pinfunction "1_1") (pintype "passive"))
      (node (ref "U1") (pin "32") (pinfunction "SIM_CLK_32") (pintype "passive"))
    )
    (net (code "68") (name "Net-(U1-SIM_DATA)") (class "Default")
      (node (ref "R21") (pin "1") (pinfunction "1_1") (pintype "passive"))
      (node (ref "U1") (pin "31") (pinfunction "SIM_DATA_31") (pintype "passive"))
    )
    (net (code "69") (name "Net-(U1-SIM_RST)") (class "Default")
      (node (ref "R18") (pin "1") (pinfunction "1_1") (pintype "passive"))
      (node (ref "U1") (pin "33") (pinfunction "SIM_RST_33") (pintype "passive"))
    )
    (net (code "70") (name "Net-(U1-VRTC)") (class "Default")
      (node (ref "C5") (pin "2") (pinfunction "2_2") (pintype "passive"))
      (node (ref "U1") (pin "26") (pinfunction "VRTC_26") (pintype "passive"))
    )
    (net (code "71") (name "VBAT") (class "Default")
      (node (ref "C3") (pin "1") (pinfunction "P_1") (pintype "passive"))
      (node (ref "CON2") (pin "10") (pinfunction "10_10") (pintype "passive"))
      (node (ref "CON2") (pin "6") (pinfunction "6_6") (pintype "passive"))
      (node (ref "CON2") (pin "8") (pinfunction "8_8") (pintype "passive"))
      (node (ref "Q9") (pin "S") (pinfunction "S_S") (pintype "passive"))
      (node (ref "R23") (pin "1") (pinfunction "1_1") (pintype "passive"))
    )
    (net (code "72") (name "VBAT_900") (class "Default")
      (node (ref "C6") (pin "1") (pinfunction "P_1") (pintype "passive"))
      (node (ref "C7") (pin "2") (pinfunction "2_2") (pintype "passive"))
      (node (ref "C8") (pin "2") (pinfunction "2_2") (pintype "passive"))
      (node (ref "C9") (pin "1") (pinfunction "P_1") (pintype "passive"))
      (node (ref "NETWORK") (pin "A") (pinfunction "A_A") (pintype "passive"))
      (node (ref "Q9") (pin "D") (pinfunction "D_D") (pintype "passive"))
      (node (ref "R19") (pin "2") (pinfunction "2_2") (pintype "passive"))
      (node (ref "STATUS") (pin "A") (pinfunction "A_A") (pintype "passive"))
      (node (ref "U1") (pin "55") (pinfunction "VBAT_55") (pintype "passive"))
      (node (ref "U1") (pin "56") (pinfunction "VBAT_56") (pintype "passive"))
      (node (ref "U1") (pin "57") (pinfunction "VBAT_57") (pintype "passive"))
    )
    (net (code "73") (name "unconnected-(COM1-VPP-Pad5)") (class "Default")
      (node (ref "COM1") (pin "5") (pinfunction "VPP_5") (pintype "passive+no_connect"))
    )
    (net (code "74") (name "unconnected-(HOLE1-TP-Pad1)") (class "Default")
      (node (ref "HOLE1") (pin "1") (pinfunction "TP_1") (pintype "passive+no_connect"))
    )
    (net (code "75") (name "unconnected-(HOLE2-TP-Pad1)") (class "Default")
      (node (ref "HOLE2") (pin "1") (pinfunction "TP_1") (pintype "passive+no_connect"))
    )
    (net (code "76") (name "unconnected-(HOLE3-TP-Pad1)") (class "Default")
      (node (ref "HOLE3") (pin "1") (pinfunction "TP_1") (pintype "passive+no_connect"))
    )
    (net (code "77") (name "unconnected-(HOLE4-TP-Pad1)") (class "Default")
      (node (ref "HOLE4") (pin "1") (pinfunction "TP_1") (pintype "passive+no_connect"))
    )
    (net (code "78") (name "unconnected-(U1-CTS-Pad7)") (class "Default")
      (node (ref "U1") (pin "7") (pinfunction "CTS_7") (pintype "passive+no_connect"))
    )
    (net (code "79") (name "unconnected-(U1-DCS-Pad5)") (class "Default")
      (node (ref "U1") (pin "5") (pinfunction "DCS_5") (pintype "passive+no_connect"))
    )
    (net (code "80") (name "unconnected-(U1-DISP_CLK-Pad11)") (class "Default")
      (node (ref "U1") (pin "11") (pinfunction "DISP_CLK_11") (pintype "passive+no_connect"))
    )
    (net (code "81") (name "unconnected-(U1-DISP_CS-Pad14)") (class "Default")
      (node (ref "U1") (pin "14") (pinfunction "DISP_CS_14") (pintype "passive+no_connect"))
    )
    (net (code "82") (name "unconnected-(U1-DISP_DATA-Pad12)") (class "Default")
      (node (ref "U1") (pin "12") (pinfunction "DISP_DATA_12") (pintype "passive+no_connect"))
    )
    (net (code "83") (name "unconnected-(U1-DISP_D{slash}C-Pad13)") (class "Default")
      (node (ref "U1") (pin "13") (pinfunction "DISP_D/C_13") (pintype "passive+no_connect"))
    )
    (net (code "84") (name "unconnected-(U1-DSR-Pad6)") (class "Default")
      (node (ref "U1") (pin "6") (pinfunction "DSR_6") (pintype "passive+no_connect"))
    )
    (net (code "85") (name "unconnected-(U1-GPIO11-Pad67)") (class "Default")
      (node (ref "U1") (pin "67") (pinfunction "GPIO11_67") (pintype "passive+no_connect"))
    )
    (net (code "86") (name "unconnected-(U1-GPIO12-Pad68)") (class "Default")
      (node (ref "U1") (pin "68") (pinfunction "GPIO12_68") (pintype "passive+no_connect"))
    )
    (net (code "87") (name "unconnected-(U1-KBC0{slash}GPIO10-Pad51)") (class "Default")
      (node (ref "U1") (pin "51") (pinfunction "KBC0/GPIO10_51") (pintype "passive+no_connect"))
    )
    (net (code "88") (name "unconnected-(U1-KBC1{slash}GPIO9-Pad50)") (class "Default")
      (node (ref "U1") (pin "50") (pinfunction "KBC1/GPIO9_50") (pintype "passive+no_connect"))
    )
    (net (code "89") (name "unconnected-(U1-KBC2{slash}GPIO8-Pad49)") (class "Default")
      (node (ref "U1") (pin "49") (pinfunction "KBC2/GPIO8_49") (pintype "passive+no_connect"))
    )
    (net (code "90") (name "unconnected-(U1-KBC3{slash}GPIO7-Pad48)") (class "Default")
      (node (ref "U1") (pin "48") (pinfunction "KBC3/GPIO7_48") (pintype "passive+no_connect"))
    )
    (net (code "91") (name "unconnected-(U1-KBC4{slash}GPIO6-Pad47)") (class "Default")
      (node (ref "U1") (pin "47") (pinfunction "KBC4/GPIO6_47") (pintype "passive+no_connect"))
    )
    (net (code "92") (name "unconnected-(U1-KBR0{slash}GPIO5-Pad44)") (class "Default")
      (node (ref "U1") (pin "44") (pinfunction "KBR0/GPIO5_44") (pintype "passive+no_connect"))
    )
    (net (code "93") (name "unconnected-(U1-KBR1{slash}GPIO4-Pad43)") (class "Default")
      (node (ref "U1") (pin "43") (pinfunction "KBR1/GPIO4_43") (pintype "passive+no_connect"))
    )
    (net (code "94") (name "unconnected-(U1-KBR2{slash}GPIO3-Pad42)") (class "Default")
      (node (ref "U1") (pin "42") (pinfunction "KBR2/GPIO3_42") (pintype "passive+no_connect"))
    )
    (net (code "95") (name "unconnected-(U1-KBR3{slash}GPIO2-Pad41)") (class "Default")
      (node (ref "U1") (pin "41") (pinfunction "KBR3/GPIO2_41") (pintype "passive+no_connect"))
    )
    (net (code "96") (name "unconnected-(U1-KBR4{slash}GPIO1-Pad40)") (class "Default")
      (node (ref "U1") (pin "40") (pinfunction "KBR4/GPIO1_40") (pintype "passive+no_connect"))
    )
    (net (code "97") (name "unconnected-(U1-LINEIN_L-Pad24)") (class "Default")
      (node (ref "U1") (pin "24") (pinfunction "LINEIN_L_24") (pintype "passive+no_connect"))
    )
    (net (code "98") (name "unconnected-(U1-LINEIN_R-Pad23)") (class "Default")
      (node (ref "U1") (pin "23") (pinfunction "LINEIN_R_23") (pintype "passive+no_connect"))
    )
    (net (code "99") (name "unconnected-(U1-MIC_N-Pad20)") (class "Default")
      (node (ref "U1") (pin "20") (pinfunction "MIC_N_20") (pintype "passive+no_connect"))
    )
    (net (code "100") (name "unconnected-(U1-MIC_P-Pad19)") (class "Default")
      (node (ref "U1") (pin "19") (pinfunction "MIC_P_19") (pintype "passive+no_connect"))
    )
    (net (code "101") (name "unconnected-(U1-PWM1-Pad35)") (class "Default")
      (node (ref "U1") (pin "35") (pinfunction "PWM1_35") (pintype "passive+no_connect"))
    )
    (net (code "102") (name "unconnected-(U1-PWM2-Pad36)") (class "Default")
      (node (ref "U1") (pin "36") (pinfunction "PWM2_36") (pintype "passive+no_connect"))
    )
    (net (code "103") (name "unconnected-(U1-PWRKEY_OUT-Pad2)") (class "Default")
      (node (ref "U1") (pin "2") (pinfunction "PWRKEY_OUT_2") (pintype "passive+no_connect"))
    )
    (net (code "104") (name "unconnected-(U1-RI-Pad4)") (class "Default")
      (node (ref "U1") (pin "4") (pinfunction "RI_4") (pintype "passive+no_connect"))
    )
    (net (code "105") (name "unconnected-(U1-SCL-Pad38)") (class "Default")
      (node (ref "U1") (pin "38") (pinfunction "SCL_38") (pintype "passive+no_connect"))
    )
    (net (code "106") (name "unconnected-(U1-SDA-Pad37)") (class "Default")
      (node (ref "U1") (pin "37") (pinfunction "SDA_37") (pintype "passive+no_connect"))
    )
    (net (code "107") (name "unconnected-(U1-SPK_N-Pad22)") (class "Default")
      (node (ref "U1") (pin "22") (pinfunction "SPK_N_22") (pintype "passive+no_connect"))
    )
    (net (code "108") (name "unconnected-(U1-SPK_P-Pad21)") (class "Default")
      (node (ref "U1") (pin "21") (pinfunction "SPK_P_21") (pintype "passive+no_connect"))
    )
  )
)
